# Rear_left_lamp.net
KiCad netlist of a schematic drawn in EAGLE
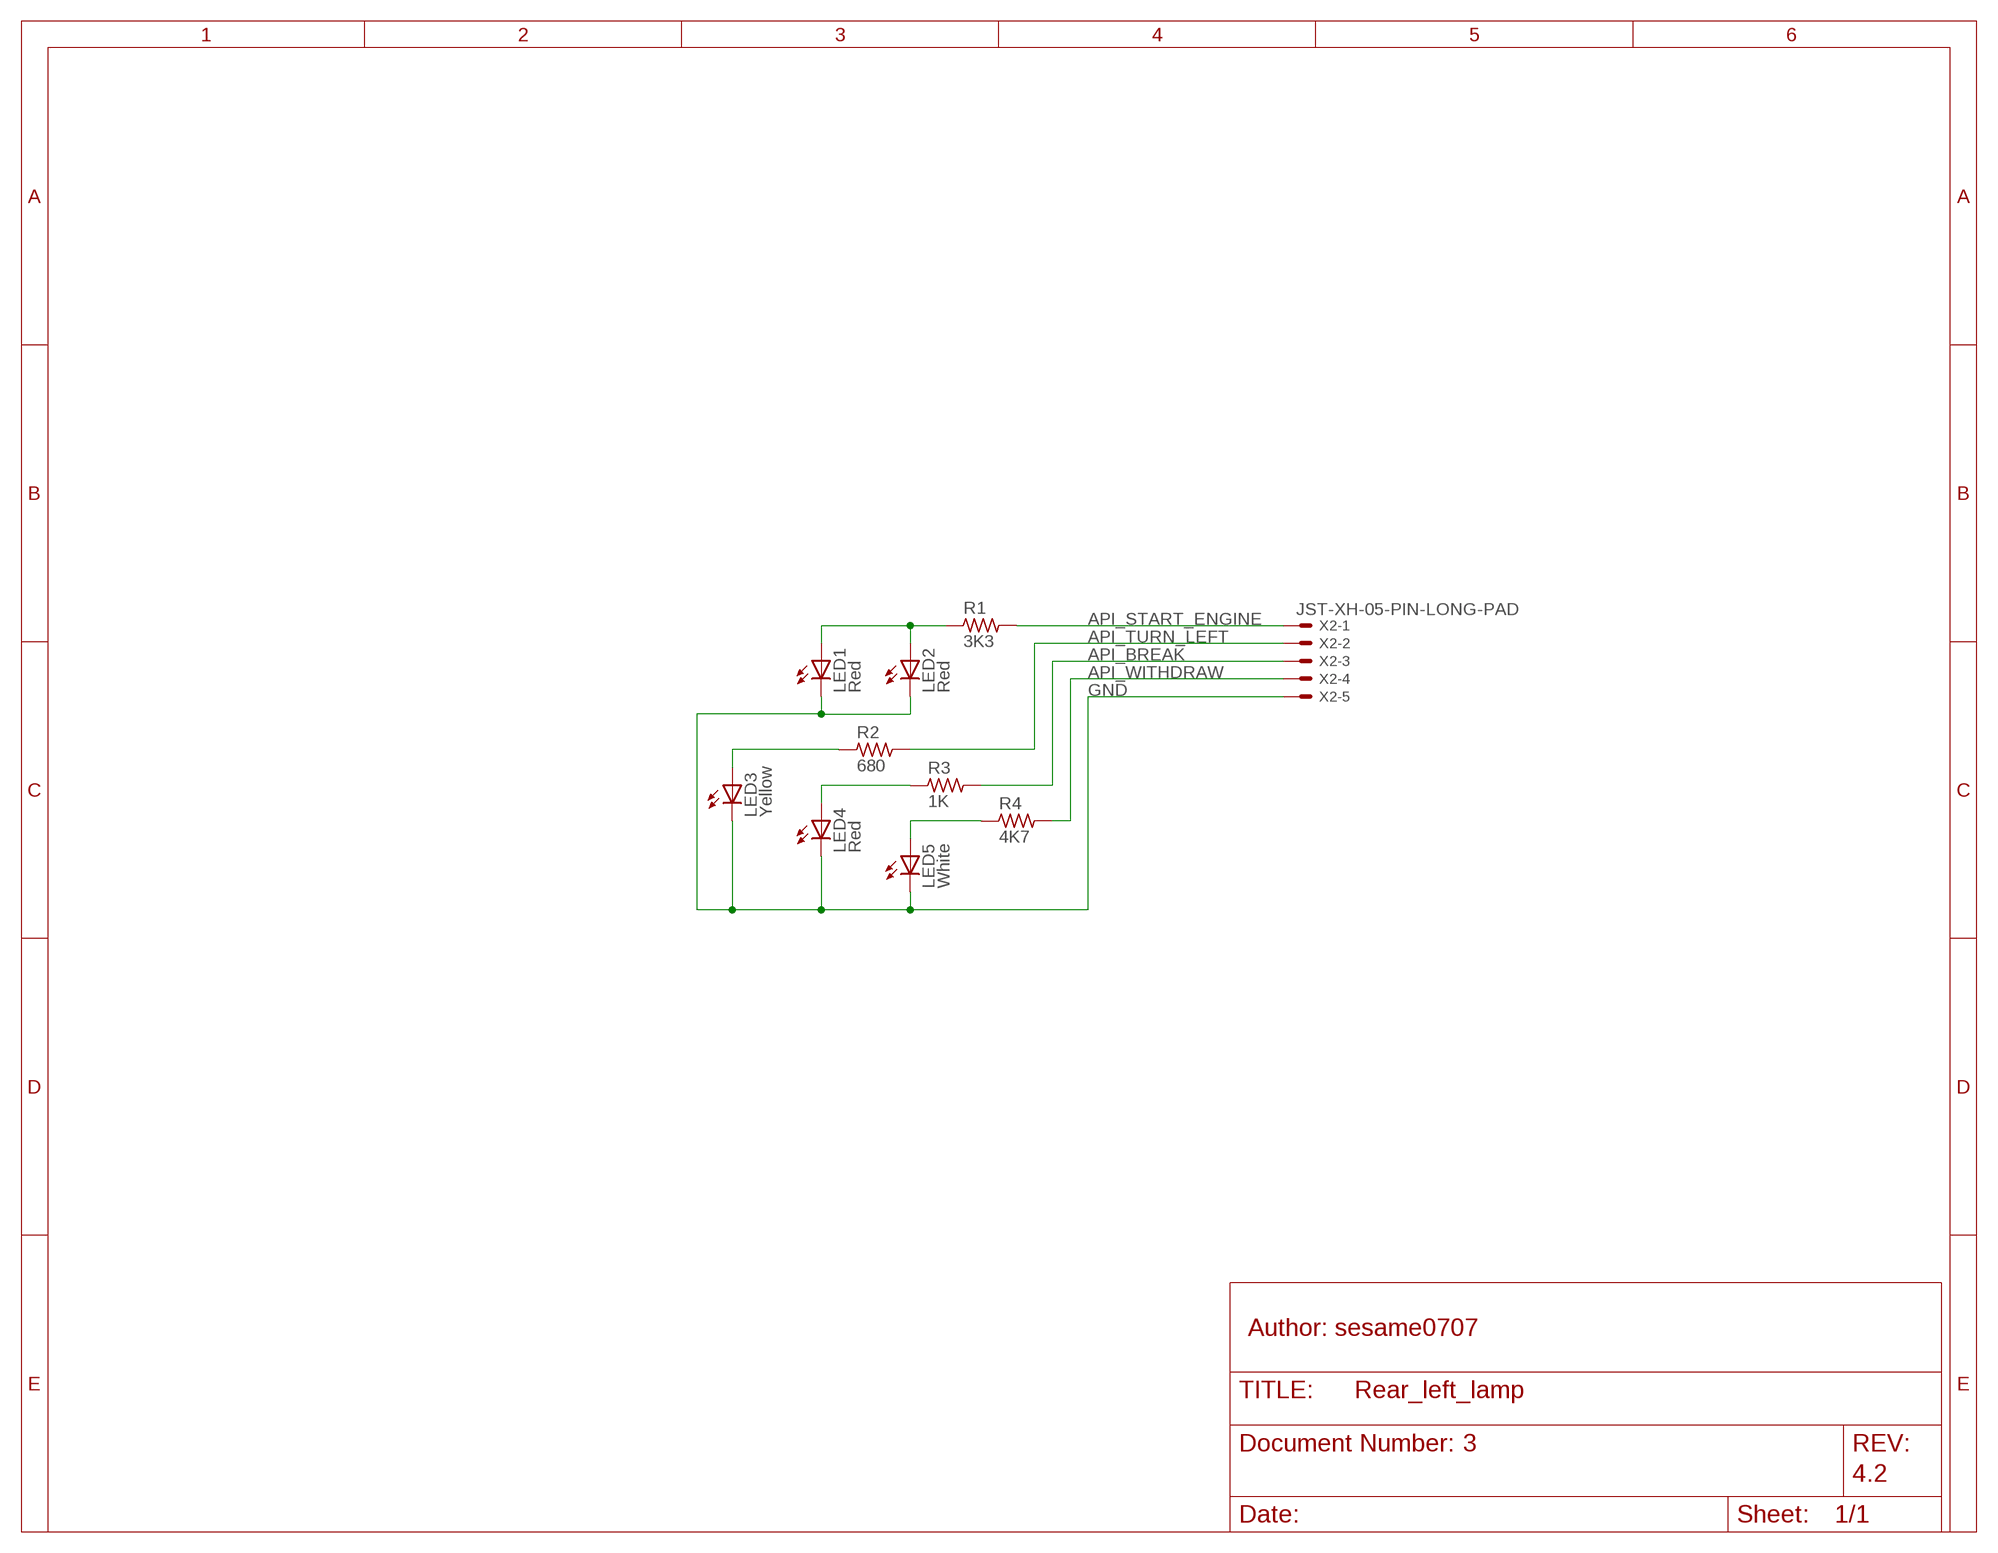
[diagram p0: schematic, sheet 1]

(export (version "E")
  (design (tool "Eeschema 10.0.6"))
  (components
    (comp (ref "LED1")
      (value "Red")
      (footprint "eagle-import:LED5MM")
      (fields
        (field (name "MANUFACTURER") "LUCKYLIGHT")
        (field (name "MANUFACTURER_PART_NUMBER") "LL-503VD2E-1B")
      )
      (libsource (lib "eagle-import") (part "LED5MM"))
    )
    (comp (ref "LED2")
      (value "Red")
      (footprint "eagle-import:LED5MM")
      (fields
        (field (name "MANUFACTURER") "LUCKYLIGHT")
        (field (name "MANUFACTURER_PART_NUMBER") "LL-503VD2E-1B")
      )
      (libsource (lib "eagle-import") (part "LED5MM"))
    )
    (comp (ref "LED3")
      (value "Yellow")
      (footprint "eagle-import:LED5MM")
      (fields
        (field (name "MANUFACTURER") "LUCKYLIGHT")
        (field (name "MANUFACTURER_PART_NUMBER") "LL-503YD2E-1B")
      )
      (libsource (lib "eagle-import") (part "LED5MM"))
    )
    (comp (ref "LED4")
      (value "Red")
      (footprint "eagle-import:LED5MM")
      (fields
        (field (name "MANUFACTURER") "LUCKYLIGHT")
        (field (name "MANUFACTURER_PART_NUMBER") "LL-503VD2E-1B")
      )
      (libsource (lib "eagle-import") (part "LED5MM"))
    )
    (comp (ref "LED5")
      (value "White")
      (footprint "eagle-import:LED5MM")
      (fields
        (field (name "MANUFACTURER") "LUCKYLIGHT")
        (field (name "MANUFACTURER_PART_NUMBER") "LL-504WC2V-W2-3PD")
      )
      (libsource (lib "eagle-import") (part "LED5MM"))
    )
    (comp (ref "R1")
      (value "3K3")
      (footprint "eagle-import:R1206")
      (fields
        (field (name "MANUFACTURER") "ROYAL OHM")
        (field (name "MANUFACTURER_PART_NUMBER") "1206S4J0332T5E")
      )
      (libsource (lib "eagle-import") (part "R_1206"))
    )
    (comp (ref "R2")
      (value "680")
      (footprint "eagle-import:R1206")
      (fields
        (field (name "MANUFACTURER") "ROYAL OHM")
        (field (name "MANUFACTURER_PART_NUMBER") "1206S4J0681T5E")
      )
      (libsource (lib "eagle-import") (part "R_1206"))
    )
    (comp (ref "R3")
      (value "1K")
      (footprint "eagle-import:R1206")
      (fields
        (field (name "MANUFACTURER") "ROYAL OHM")
        (field (name "MANUFACTURER_PART_NUMBER") "1206S4J0102T5E")
      )
      (libsource (lib "eagle-import") (part "R_1206"))
    )
    (comp (ref "R4")
      (value "4K7")
      (footprint "eagle-import:R1206")
      (fields
        (field (name "MANUFACTURER") "ROYAL OHM")
        (field (name "MANUFACTURER_PART_NUMBER") "1206S4J0472T5E")
      )
      (libsource (lib "eagle-import") (part "R_1206"))
    )
    (comp (ref "X2")
      (value "JST-XH-05-PIN-LONG-PAD")
      (footprint "eagle-import:JST-XH-05-PACKAGE-LONG-PAD")
      (libsource (lib "eagle-import") (part "JST-XH-05-PIN-LONG-PAD"))
    )
  )
  (nets
    (net (code "1") (name "/API_BREAK") (class "Default")
      (node (ref "R3") (pin "2") (pinfunction "2_2") (pintype "passive"))
      (node (ref "X2") (pin "3") (pinfunction "S_3") (pintype "passive"))
    )
    (net (code "2") (name "/API_START_ENGINE") (class "Default")
      (node (ref "LED1") (pin "A") (pinfunction "A_A") (pintype "passive"))
      (node (ref "LED2") (pin "A") (pinfunction "A_A") (pintype "passive"))
      (node (ref "R1") (pin "1") (pinfunction "1_1") (pintype "passive"))
    )
    (net (code "3") (name "/API_TURN_LEFT") (class "Default")
      (node (ref "R2") (pin "2") (pinfunction "2_2") (pintype "passive"))
      (node (ref "X2") (pin "2") (pinfunction "S_2") (pintype "passive"))
    )
    (net (code "4") (name "/API_WITHDRAW") (class "Default")
      (node (ref "R4") (pin "2") (pinfunction "2_2") (pintype "passive"))
      (node (ref "X2") (pin "4") (pinfunction "S_4") (pintype "passive"))
    )
    (net (code "5") (name "/GND") (class "Default")
      (node (ref "LED1") (pin "K") (pinfunction "C_K") (pintype "passive"))
      (node (ref "LED2") (pin "K") (pinfunction "C_K") (pintype "passive"))
      (node (ref "LED3") (pin "K") (pinfunction "C_K") (pintype "passive"))
      (node (ref "LED4") (pin "K") (pinfunction "C_K") (pintype "passive"))
      (node (ref "LED5") (pin "K") (pinfunction "C_K") (pintype "passive"))
      (node (ref "X2") (pin "5") (pinfunction "S_5") (pintype "passive"))
    )
    (net (code "6") (name "Net-(LED3-PadA)") (class "Default")
      (node (ref "LED3") (pin "A") (pinfunction "A_A") (pintype "passive"))
      (node (ref "R2") (pin "1") (pinfunction "1_1") (pintype "passive"))
    )
    (net (code "7") (name "Net-(LED4-PadA)") (class "Default")
      (node (ref "LED4") (pin "A") (pinfunction "A_A") (pintype "passive"))
      (node (ref "R3") (pin "1") (pinfunction "1_1") (pintype "passive"))
    )
    (net (code "8") (name "Net-(LED5-PadA)") (class "Default")
      (node (ref "LED5") (pin "A") (pinfunction "A_A") (pintype "passive"))
      (node (ref "R4") (pin "1") (pinfunction "1_1") (pintype "passive"))
    )
    (net (code "9") (name "Net-(X2A-S)") (class "Default")
      (node (ref "R1") (pin "2") (pinfunction "2_2") (pintype "passive"))
      (node (ref "X2") (pin "1") (pinfunction "S_1") (pintype "passive"))
    )
  )
)
